# Twelve_to_Five_Volt_Converter.net
KiCad netlist of a schematic drawn in EAGLE
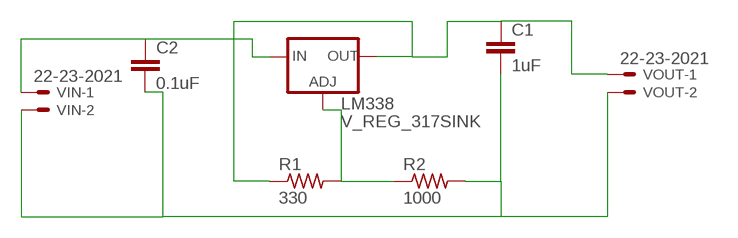
[diagram p0: schematic, sheet 1]

(export (version "E")
  (design (tool "Eeschema 10.0.6"))
  (components
    (comp (ref "C1")
      (value "1uF")
      (footprint "eagle-import:C5B3.5")
      (libsource (lib "eagle-import") (part "C5/3.5"))
    )
    (comp (ref "C2")
      (value "0.1uF")
      (footprint "eagle-import:C5B3.5")
      (libsource (lib "eagle-import") (part "C5/3.5"))
    )
    (comp (ref "LM338")
      (value "V_REG_317SINK")
      (footprint "eagle-import:TO220-ADJ")
      (libsource (lib "eagle-import") (part "V_REG_317SINK"))
    )
    (comp (ref "R1")
      (value "330")
      (footprint "eagle-import:0207_10")
      (libsource (lib "eagle-import") (part "R-US_0207/10"))
    )
    (comp (ref "R2")
      (value "1000")
      (footprint "eagle-import:0207_10")
      (libsource (lib "eagle-import") (part "R-US_0207/10"))
    )
    (comp (ref "VIN")
      (value "22-23-2021")
      (footprint "eagle-import:22-23-2021")
      (fields (field (name "MF") "MOLEX"))
      (libsource (lib "eagle-import") (part "22-23-2021"))
    )
    (comp (ref "VOUT")
      (value "22-23-2021")
      (footprint "eagle-import:22-23-2021")
      (fields (field (name "MF") "MOLEX"))
      (libsource (lib "eagle-import") (part "22-23-2021"))
    )
  )
  (nets
    (net (code "1") (name "Net-(LM338-PadADJ)") (class "Default")
      (node (ref "LM338") (pin "ADJ") (pinfunction "ADJ_ADJ") (pintype "input"))
      (node (ref "R1") (pin "2") (pinfunction "2_2") (pintype "passive"))
      (node (ref "R2") (pin "1") (pinfunction "1_1") (pintype "passive"))
    )
    (net (code "2") (name "Net-(VINA-S)") (class "Default")
      (node (ref "C2") (pin "1") (pinfunction "1_1") (pintype "passive"))
      (node (ref "LM338") (pin "IN") (pinfunction "IN_IN") (pintype "input"))
      (node (ref "VIN") (pin "1") (pinfunction "S_1") (pintype "passive"))
    )
    (net (code "3") (name "Net-(VINB-S)") (class "Default")
      (node (ref "C1") (pin "2") (pinfunction "2_2") (pintype "passive"))
      (node (ref "C2") (pin "2") (pinfunction "2_2") (pintype "passive"))
      (node (ref "R2") (pin "2") (pinfunction "2_2") (pintype "passive"))
      (node (ref "VIN") (pin "2") (pinfunction "S_2") (pintype "passive"))
      (node (ref "VOUT") (pin "2") (pinfunction "S_2") (pintype "passive"))
    )
    (net (code "4") (name "Net-(VOUTA-S)") (class "Default")
      (node (ref "C1") (pin "1") (pinfunction "1_1") (pintype "passive"))
      (node (ref "LM338") (pin "OUT") (pinfunction "OUT_OUT") (pintype "output"))
      (node (ref "R1") (pin "1") (pinfunction "1_1") (pintype "passive"))
      (node (ref "VOUT") (pin "1") (pinfunction "S_1") (pintype "passive"))
    )
  )
)
